# RC_P.net
KiCad netlist of a schematic drawn in EAGLE
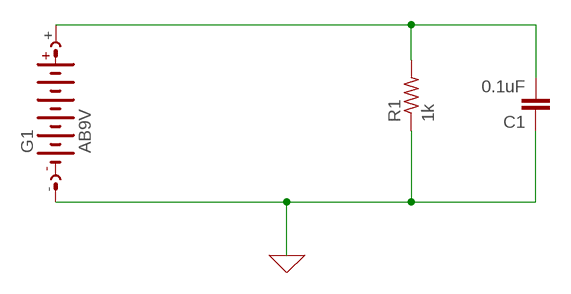
[diagram p0: schematic, sheet 1]

(export (version "E")
  (design (tool "Eeschema 10.0.6"))
  (components
    (comp (ref "C1")
      (value "0.1uF")
      (footprint "eagle-import:0402")
      (libsource (lib "eagle-import") (part "0.1UF-0402-6.3V-10%-X7R"))
    )
    (comp (ref "G1")
      (value "AB9V")
      (footprint "eagle-import:AB9V")
      (libsource (lib "eagle-import") (part "AB9V"))
    )
    (comp (ref "R1")
      (value "1k")
      (footprint "eagle-import:0204V")
      (libsource (lib "eagle-import") (part "R-US_0204/2V"))
    )
  )
  (nets
    (net (code "1") (name "GND") (class "Default")
      (node (ref "C1") (pin "1") (pinfunction "1_1") (pintype "passive"))
      (node (ref "G1") (pin "-") (pinfunction "-_-") (pintype "passive"))
      (node (ref "R1") (pin "1") (pinfunction "1_1") (pintype "passive"))
    )
    (net (code "2") (name "Net-(C1-Pad2)") (class "Default")
      (node (ref "C1") (pin "2") (pinfunction "2_2") (pintype "passive"))
      (node (ref "G1") (pin "+") (pinfunction "+_+") (pintype "passive"))
      (node (ref "R1") (pin "2") (pinfunction "2_2") (pintype "passive"))
    )
  )
)
